# ESP32_RelayBoard.net
KiCad netlist of a schematic drawn in EasyEDA Pro
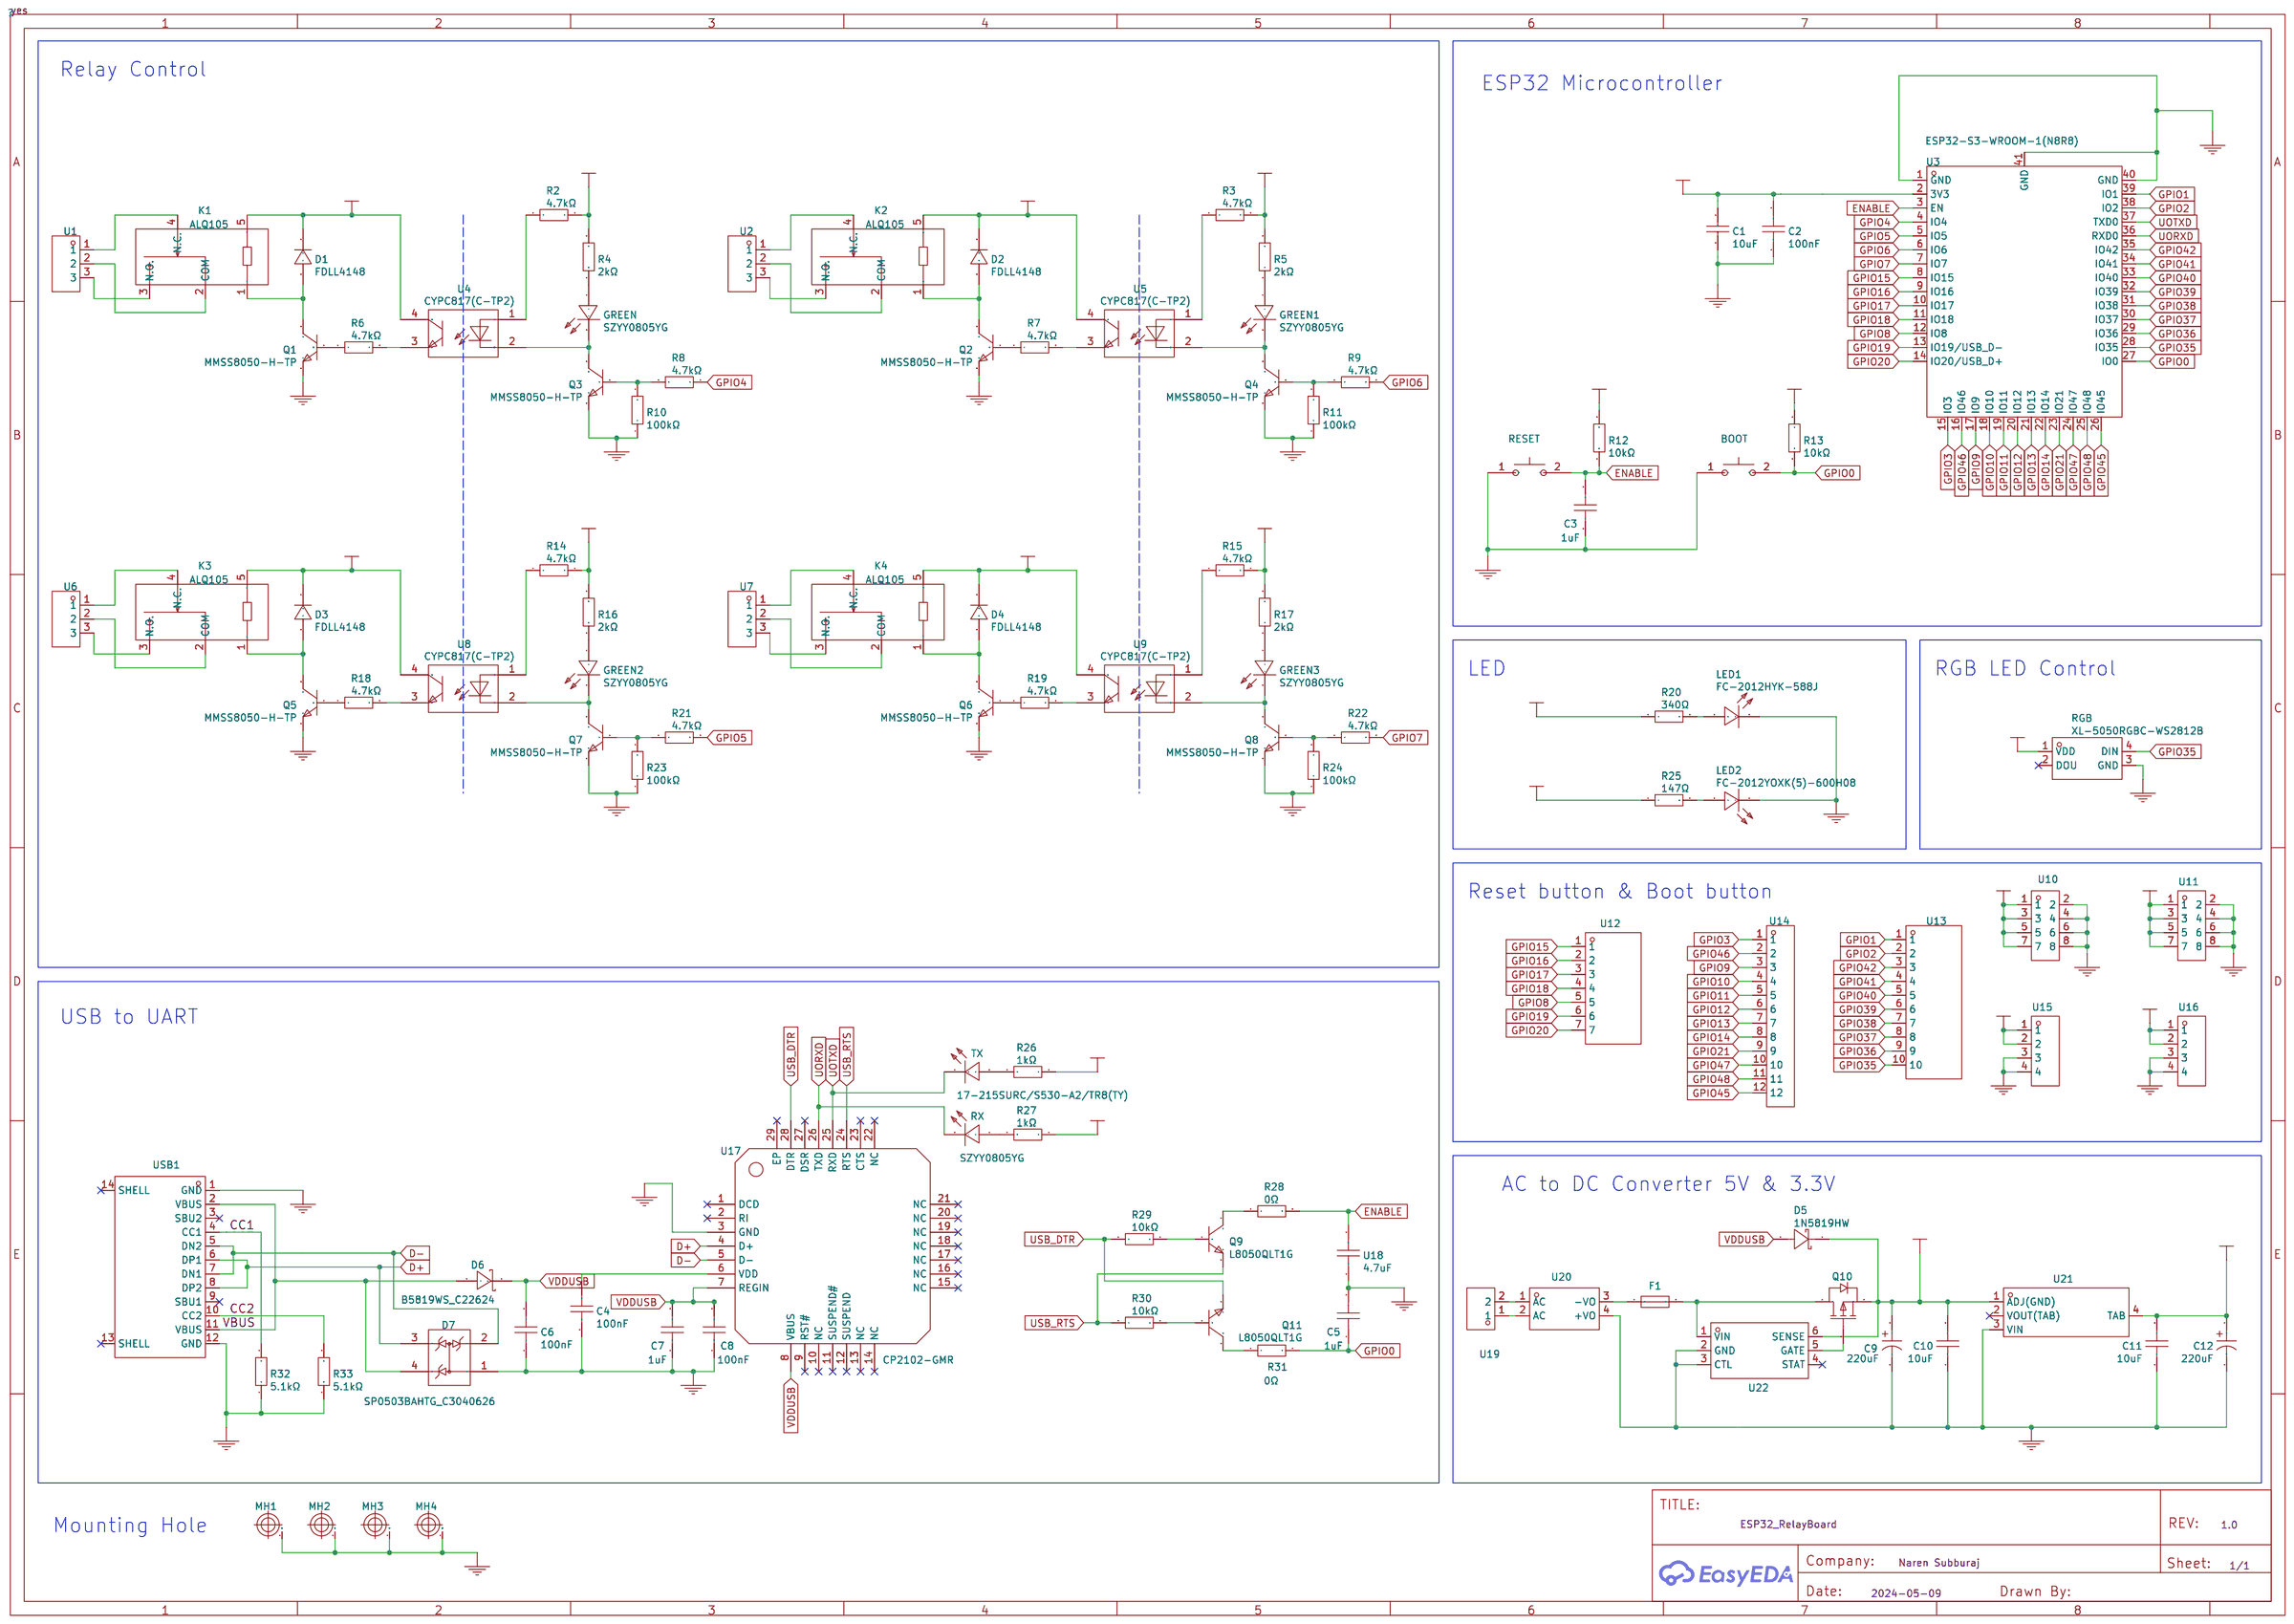
[diagram p0: schematic sheet]

(export (version "E")
  (design (tool "Eeschema 10.0.6"))
  (components
    (comp (ref "BOOT")
      (value "TS-1101S-C-B-B-B-A")
      (footprint "easyedapro:SW-SMD_L6.0-W3.5-LS8.0")
      (fields (field (name "Manufacturer") "XKB Connectivity(中国星坤)"))
      (libsource (lib "easyedapro") (part "TS-1101S-C-B-B-B-A"))
    )
    (comp (ref "C1")
      (value "10uF")
      (footprint "easyedapro:C0402")
      (fields
        (field (name "Manufacturer Part") "CC0402MRX5R5BB106")
        (field (name "Manufacturer") "YAGEO(国巨)")
      )
      (libsource (lib "") (part "10uF_1"))
    )
    (comp (ref "C2")
      (value "100nF")
      (footprint "easyedapro:C0402")
      (fields
        (field (name "Manufacturer Part") "CSA0402X7R104K250GT")
        (field (name "Manufacturer") "HRE(芯声)")
      )
      (libsource (lib "easyedapro") (part "100nF"))
    )
    (comp (ref "C3")
      (value "1uF")
      (footprint "easyedapro:C0402")
      (fields
        (field (name "Manufacturer Part") "HGC0402R5105K500NTEJ")
        (field (name "Manufacturer") "Chinocera(华瓷)")
      )
      (libsource (lib "easyedapro") (part "1uF"))
    )
    (comp (ref "C4")
      (value "100nF")
      (footprint "easyedapro:C0402")
      (fields
        (field (name "Manufacturer Part") "CSA0402X7R104K250GT")
        (field (name "Manufacturer") "HRE(芯声)")
      )
      (libsource (lib "easyedapro") (part "100nF"))
    )
    (comp (ref "C5")
      (value "1uF")
      (footprint "easyedapro:C0402")
      (fields
        (field (name "Manufacturer Part") "HGC0402R5105K500NTEJ")
        (field (name "Manufacturer") "Chinocera(华瓷)")
      )
      (libsource (lib "easyedapro") (part "1uF"))
    )
    (comp (ref "C6")
      (value "100nF")
      (footprint "easyedapro:C0402")
      (fields
        (field (name "Manufacturer Part") "CSA0402X7R104K250GT")
        (field (name "Manufacturer") "HRE(芯声)")
      )
      (libsource (lib "easyedapro") (part "100nF"))
    )
    (comp (ref "C7")
      (value "1uF")
      (footprint "easyedapro:C0402")
      (fields
        (field (name "Manufacturer Part") "HGC0402R5105K500NTEJ")
        (field (name "Manufacturer") "Chinocera(华瓷)")
      )
      (libsource (lib "easyedapro") (part "1uF"))
    )
    (comp (ref "C8")
      (value "100nF")
      (footprint "easyedapro:C0402")
      (fields
        (field (name "Manufacturer Part") "CSA0402X7R104K250GT")
        (field (name "Manufacturer") "HRE(芯声)")
      )
      (libsource (lib "easyedapro") (part "100nF"))
    )
    (comp (ref "C9")
      (value "220uF")
      (footprint "easyedapro:CAP-SMD_BD6.3-L6.6-W6.6-LS7.2-FD")
      (fields
        (field (name "Manufacturer Part") "MVG 16V 220UF 6.3*7.7")
        (field (name "Manufacturer") "SAMYOUNG(韩国三莹)")
      )
      (libsource (lib "easyedapro") (part "220uF"))
    )
    (comp (ref "C10")
      (value "10uF")
      (footprint "easyedapro:C0805")
      (fields (field (name "Manufacturer Part") "0805F106M160NT") (field (name "Manufacturer") "FH(风华)"))
      (libsource (lib "easyedapro") (part "10uF"))
    )
    (comp (ref "C11")
      (value "10uF")
      (footprint "easyedapro:C0805")
      (fields (field (name "Manufacturer Part") "0805F106M160NT") (field (name "Manufacturer") "FH(风华)"))
      (libsource (lib "easyedapro") (part "10uF"))
    )
    (comp (ref "C12")
      (value "220uF")
      (footprint "easyedapro:CAP-SMD_BD6.3-L6.6-W6.6-LS7.2-FD")
      (fields
        (field (name "Manufacturer Part") "MVG 16V 220UF 6.3*7.7")
        (field (name "Manufacturer") "SAMYOUNG(韩国三莹)")
      )
      (libsource (lib "easyedapro") (part "220uF"))
    )
    (comp (ref "D1")
      (value "FDLL4148")
      (footprint "easyedapro:SOD-80_L3.5-W1.5-RD")
      (fields (field (name "Manufacturer") "onsemi(安森美)"))
      (libsource (lib "easyedapro") (part "FDLL4148"))
    )
    (comp (ref "D2")
      (value "FDLL4148")
      (footprint "easyedapro:SOD-80_L3.5-W1.5-RD")
      (fields (field (name "Manufacturer") "onsemi(安森美)"))
      (libsource (lib "easyedapro") (part "FDLL4148"))
    )
    (comp (ref "D3")
      (value "FDLL4148")
      (footprint "easyedapro:SOD-80_L3.5-W1.5-RD")
      (fields (field (name "Manufacturer") "onsemi(安森美)"))
      (libsource (lib "easyedapro") (part "FDLL4148"))
    )
    (comp (ref "D4")
      (value "FDLL4148")
      (footprint "easyedapro:SOD-80_L3.5-W1.5-RD")
      (fields (field (name "Manufacturer") "onsemi(安森美)"))
      (libsource (lib "easyedapro") (part "FDLL4148"))
    )
    (comp (ref "D5")
      (value "1N5819HW")
      (footprint "easyedapro:SOD-123_L2.7-W1.6-LS3.7-RD-1")
      (fields (field (name "Manufacturer") "TECH PUBLIC(台舟)"))
      (libsource (lib "easyedapro") (part "1N5819HW"))
    )
    (comp (ref "D6")
      (value "B5819WS_C22624")
      (footprint "easyedapro:SOD-323_L1.8-W1.3-LS2.5-RD")
      (fields (field (name "Manufacturer Part") "B5819WS") (field (name "Manufacturer") "CJ(江苏长电/长晶)"))
      (libsource (lib "easyedapro") (part "B5819WS_C22624"))
    )
    (comp (ref "D7")
      (value "SP0503BAHTG_C3040626")
      (footprint "easyedapro:SOT-143-4_L2.9-W1.3-P1.92-LS2.4-BL")
      (fields
        (field (name "Manufacturer Part") "SP0503BAHTG")
        (field (name "Manufacturer") "TECH PUBLIC(台舟)")
      )
      (libsource (lib "easyedapro") (part "SP0503BAHTG_C3040626"))
    )
    (comp (ref "F1")
      (value "BSMD0805-100-6V")
      (footprint "easyedapro:F0805")
      (fields (field (name "Manufacturer") "BHFUSE(佰宏)"))
      (libsource (lib "easyedapro") (part "BSMD0805-100-6V"))
    )
    (comp (ref "GREEN")
      (value "SZYY0805YG")
      (footprint "easyedapro:LED0805-R-RD_GREEN")
      (fields (field (name "Manufacturer") "yongyu(永裕光电)"))
      (libsource (lib "easyedapro") (part "SZYY0805YG"))
    )
    (comp (ref "GREEN1")
      (value "SZYY0805YG")
      (footprint "easyedapro:LED0805-R-RD_GREEN")
      (fields (field (name "Manufacturer") "yongyu(永裕光电)"))
      (libsource (lib "easyedapro") (part "SZYY0805YG"))
    )
    (comp (ref "GREEN2")
      (value "SZYY0805YG")
      (footprint "easyedapro:LED0805-R-RD_GREEN")
      (fields (field (name "Manufacturer") "yongyu(永裕光电)"))
      (libsource (lib "easyedapro") (part "SZYY0805YG"))
    )
    (comp (ref "GREEN3")
      (value "SZYY0805YG")
      (footprint "easyedapro:LED0805-R-RD_GREEN")
      (fields (field (name "Manufacturer") "yongyu(永裕光电)"))
      (libsource (lib "easyedapro") (part "SZYY0805YG"))
    )
    (comp (ref "K1")
      (value "ALQ105")
      (footprint "easyedapro:RELAY-TH_ALQ1XX")
      (fields (field (name "Manufacturer") "PANASONIC(松下)"))
      (libsource (lib "easyedapro") (part "ALQ105"))
    )
    (comp (ref "K2")
      (value "ALQ105")
      (footprint "easyedapro:RELAY-TH_ALQ1XX")
      (fields (field (name "Manufacturer") "PANASONIC(松下)"))
      (libsource (lib "easyedapro") (part "ALQ105"))
    )
    (comp (ref "K3")
      (value "ALQ105")
      (footprint "easyedapro:RELAY-TH_ALQ1XX")
      (fields (field (name "Manufacturer") "PANASONIC(松下)"))
      (libsource (lib "easyedapro") (part "ALQ105"))
    )
    (comp (ref "K4")
      (value "ALQ105")
      (footprint "easyedapro:RELAY-TH_ALQ1XX")
      (fields (field (name "Manufacturer") "PANASONIC(松下)"))
      (libsource (lib "easyedapro") (part "ALQ105"))
    )
    (comp (ref "LED1")
      (value "FC-2012HYK-588J")
      (footprint "easyedapro:LED0805-R-RD")
      (fields (field (name "Manufacturer Part") "NCD0805Y1") (field (name "Manufacturer") "国星光电"))
      (libsource (lib "easyedapro") (part "FC-2012HYK-588J"))
    )
    (comp (ref "LED2")
      (value "FC-2012YOXK(5)-600H08")
      (footprint "easyedapro:LED0805-RD_ORANGE")
      (fields (field (name "Manufacturer Part") "NCD0805O1") (field (name "Manufacturer") "国星光电"))
      (libsource (lib "easyedapro") (part "FC-2012YOXK(5)-600H08"))
    )
    (comp (ref "MH1")
      (value "M2-MOUNTING-HOLE")
      (footprint "easyedapro:M2-MOUNTING-HOLE")
      (libsource (lib "easyedapro") (part "M2-MOUNTING-HOLE"))
    )
    (comp (ref "MH2")
      (value "M2-MOUNTING-HOLE")
      (footprint "easyedapro:M2-MOUNTING-HOLE")
      (libsource (lib "") (part "M2-MOUNTING-HOLE_1"))
    )
    (comp (ref "MH3")
      (value "M2-MOUNTING-HOLE")
      (footprint "easyedapro:M2-MOUNTING-HOLE")
      (libsource (lib "") (part "M2-MOUNTING-HOLE_2"))
    )
    (comp (ref "MH4")
      (value "M2-MOUNTING-HOLE")
      (footprint "easyedapro:M2-MOUNTING-HOLE")
      (libsource (lib "easyedapro") (part "M2-MOUNTING-HOLE"))
    )
    (comp (ref "Q1")
      (value "MMSS8050-H-TP")
      (footprint "easyedapro:SOT-23-3_L2.9-W1.6-P1.90-LS2.8-BR")
      (fields (field (name "Manufacturer") "MCC(美微科)"))
      (libsource (lib "easyedapro") (part "MMSS8050-H-TP"))
    )
    (comp (ref "Q2")
      (value "MMSS8050-H-TP")
      (footprint "easyedapro:SOT-23-3_L2.9-W1.6-P1.90-LS2.8-BR")
      (fields (field (name "Manufacturer") "MCC(美微科)"))
      (libsource (lib "easyedapro") (part "MMSS8050-H-TP"))
    )
    (comp (ref "Q3")
      (value "MMSS8050-H-TP")
      (footprint "easyedapro:SOT-23-3_L2.9-W1.6-P1.90-LS2.8-BR")
      (fields (field (name "Manufacturer") "MCC(美微科)"))
      (libsource (lib "easyedapro") (part "MMSS8050-H-TP"))
    )
    (comp (ref "Q4")
      (value "MMSS8050-H-TP")
      (footprint "easyedapro:SOT-23-3_L2.9-W1.6-P1.90-LS2.8-BR")
      (fields (field (name "Manufacturer") "MCC(美微科)"))
      (libsource (lib "easyedapro") (part "MMSS8050-H-TP"))
    )
    (comp (ref "Q5")
      (value "MMSS8050-H-TP")
      (footprint "easyedapro:SOT-23-3_L2.9-W1.6-P1.90-LS2.8-BR")
      (fields (field (name "Manufacturer") "MCC(美微科)"))
      (libsource (lib "easyedapro") (part "MMSS8050-H-TP"))
    )
    (comp (ref "Q6")
      (value "MMSS8050-H-TP")
      (footprint "easyedapro:SOT-23-3_L2.9-W1.6-P1.90-LS2.8-BR")
      (fields (field (name "Manufacturer") "MCC(美微科)"))
      (libsource (lib "easyedapro") (part "MMSS8050-H-TP"))
    )
    (comp (ref "Q7")
      (value "MMSS8050-H-TP")
      (footprint "easyedapro:SOT-23-3_L2.9-W1.6-P1.90-LS2.8-BR")
      (fields (field (name "Manufacturer") "MCC(美微科)"))
      (libsource (lib "easyedapro") (part "MMSS8050-H-TP"))
    )
    (comp (ref "Q8")
      (value "MMSS8050-H-TP")
      (footprint "easyedapro:SOT-23-3_L2.9-W1.6-P1.90-LS2.8-BR")
      (fields (field (name "Manufacturer") "MCC(美微科)"))
      (libsource (lib "easyedapro") (part "MMSS8050-H-TP"))
    )
    (comp (ref "Q9")
      (value "L8050QLT1G")
      (footprint "easyedapro:SOT-23-3_L2.9-W1.3-P1.90-LS2.4-BR")
      (fields (field (name "Manufacturer") "LRC(乐山无线电)"))
      (libsource (lib "easyedapro") (part "L8050QLT1G"))
    )
    (comp (ref "Q10")
      (value "FDN306P")
      (footprint "easyedapro:SOT-23-3_L3.0-W1.7-P0.95-LS2.9-BR")
      (fields (field (name "Manufacturer") "onsemi(安森美)"))
      (libsource (lib "easyedapro") (part "FDN306P"))
    )
    (comp (ref "Q11")
      (value "L8050QLT1G")
      (footprint "easyedapro:SOT-23-3_L2.9-W1.3-P1.90-LS2.4-BR")
      (fields (field (name "Manufacturer") "LRC(乐山无线电)"))
      (libsource (lib "") (part "L8050QLT1G_1"))
    )
    (comp (ref "R2")
      (value "4.7kΩ")
      (footprint "easyedapro:R0805")
      (fields
        (field (name "Manufacturer Part") "0805W8F4701T5E")
        (field (name "Manufacturer") "UNI-ROYAL(厚声)")
      )
      (libsource (lib "easyedapro") (part "4.7kΩ"))
    )
    (comp (ref "R3")
      (value "4.7kΩ")
      (footprint "easyedapro:R0805")
      (fields
        (field (name "Manufacturer Part") "0805W8F4701T5E")
        (field (name "Manufacturer") "UNI-ROYAL(厚声)")
      )
      (libsource (lib "easyedapro") (part "4.7kΩ"))
    )
    (comp (ref "R4")
      (value "2kΩ")
      (footprint "easyedapro:R0805")
      (fields
        (field (name "Manufacturer Part") "0805W8F2001T5E")
        (field (name "Manufacturer") "UNI-ROYAL(厚声)")
      )
      (libsource (lib "easyedapro") (part "2kΩ"))
    )
    (comp (ref "R5")
      (value "2kΩ")
      (footprint "easyedapro:R0805")
      (fields
        (field (name "Manufacturer Part") "0805W8F2001T5E")
        (field (name "Manufacturer") "UNI-ROYAL(厚声)")
      )
      (libsource (lib "easyedapro") (part "2kΩ"))
    )
    (comp (ref "R6")
      (value "4.7kΩ")
      (footprint "easyedapro:R0805")
      (fields
        (field (name "Manufacturer Part") "0805W8F4701T5E")
        (field (name "Manufacturer") "UNI-ROYAL(厚声)")
      )
      (libsource (lib "easyedapro") (part "4.7kΩ"))
    )
    (comp (ref "R7")
      (value "4.7kΩ")
      (footprint "easyedapro:R0805")
      (fields
        (field (name "Manufacturer Part") "0805W8F4701T5E")
        (field (name "Manufacturer") "UNI-ROYAL(厚声)")
      )
      (libsource (lib "easyedapro") (part "4.7kΩ"))
    )
    (comp (ref "R8")
      (value "4.7kΩ")
      (footprint "easyedapro:R0805")
      (fields
        (field (name "Manufacturer Part") "0805W8F4701T5E")
        (field (name "Manufacturer") "UNI-ROYAL(厚声)")
      )
      (libsource (lib "easyedapro") (part "4.7kΩ"))
    )
    (comp (ref "R9")
      (value "4.7kΩ")
      (footprint "easyedapro:R0805")
      (fields
        (field (name "Manufacturer Part") "0805W8F4701T5E")
        (field (name "Manufacturer") "UNI-ROYAL(厚声)")
      )
      (libsource (lib "easyedapro") (part "4.7kΩ"))
    )
    (comp (ref "R10")
      (value "100kΩ")
      (footprint "easyedapro:R0805")
      (fields
        (field (name "Manufacturer Part") "0805W8F1003T5E")
        (field (name "Manufacturer") "UNI-ROYAL(厚声)")
      )
      (libsource (lib "easyedapro") (part "100kΩ"))
    )
    (comp (ref "R11")
      (value "100kΩ")
      (footprint "easyedapro:R0805")
      (fields
        (field (name "Manufacturer Part") "0805W8F1003T5E")
        (field (name "Manufacturer") "UNI-ROYAL(厚声)")
      )
      (libsource (lib "easyedapro") (part "100kΩ"))
    )
    (comp (ref "R12")
      (value "10kΩ")
      (footprint "easyedapro:R0402")
      (fields (field (name "Manufacturer Part") "RT0402DRE0710KL") (field (name "Manufacturer") "YAGEO(国巨)"))
      (libsource (lib "easyedapro") (part "10kΩ"))
    )
    (comp (ref "R13")
      (value "10kΩ")
      (footprint "easyedapro:R0402")
      (fields (field (name "Manufacturer Part") "RT0402DRE0710KL") (field (name "Manufacturer") "YAGEO(国巨)"))
      (libsource (lib "easyedapro") (part "10kΩ"))
    )
    (comp (ref "R14")
      (value "4.7kΩ")
      (footprint "easyedapro:R0805")
      (fields
        (field (name "Manufacturer Part") "0805W8F4701T5E")
        (field (name "Manufacturer") "UNI-ROYAL(厚声)")
      )
      (libsource (lib "easyedapro") (part "4.7kΩ"))
    )
    (comp (ref "R15")
      (value "4.7kΩ")
      (footprint "easyedapro:R0805")
      (fields
        (field (name "Manufacturer Part") "0805W8F4701T5E")
        (field (name "Manufacturer") "UNI-ROYAL(厚声)")
      )
      (libsource (lib "easyedapro") (part "4.7kΩ"))
    )
    (comp (ref "R16")
      (value "2kΩ")
      (footprint "easyedapro:R0805")
      (fields
        (field (name "Manufacturer Part") "0805W8F2001T5E")
        (field (name "Manufacturer") "UNI-ROYAL(厚声)")
      )
      (libsource (lib "easyedapro") (part "2kΩ"))
    )
    (comp (ref "R17")
      (value "2kΩ")
      (footprint "easyedapro:R0805")
      (fields
        (field (name "Manufacturer Part") "0805W8F2001T5E")
        (field (name "Manufacturer") "UNI-ROYAL(厚声)")
      )
      (libsource (lib "easyedapro") (part "2kΩ"))
    )
    (comp (ref "R18")
      (value "4.7kΩ")
      (footprint "easyedapro:R0805")
      (fields
        (field (name "Manufacturer Part") "0805W8F4701T5E")
        (field (name "Manufacturer") "UNI-ROYAL(厚声)")
      )
      (libsource (lib "easyedapro") (part "4.7kΩ"))
    )
    (comp (ref "R19")
      (value "4.7kΩ")
      (footprint "easyedapro:R0805")
      (fields
        (field (name "Manufacturer Part") "0805W8F4701T5E")
        (field (name "Manufacturer") "UNI-ROYAL(厚声)")
      )
      (libsource (lib "easyedapro") (part "4.7kΩ"))
    )
    (comp (ref "R20")
      (value "340Ω")
      (footprint "easyedapro:R0805")
      (fields (field (name "Manufacturer Part") "CR0805F83400G") (field (name "Manufacturer") "LIZ(丽智电子)"))
      (libsource (lib "easyedapro") (part "340Ω"))
    )
    (comp (ref "R21")
      (value "4.7kΩ")
      (footprint "easyedapro:R0805")
      (fields
        (field (name "Manufacturer Part") "0805W8F4701T5E")
        (field (name "Manufacturer") "UNI-ROYAL(厚声)")
      )
      (libsource (lib "easyedapro") (part "4.7kΩ"))
    )
    (comp (ref "R22")
      (value "4.7kΩ")
      (footprint "easyedapro:R0805")
      (fields
        (field (name "Manufacturer Part") "0805W8F4701T5E")
        (field (name "Manufacturer") "UNI-ROYAL(厚声)")
      )
      (libsource (lib "easyedapro") (part "4.7kΩ"))
    )
    (comp (ref "R23")
      (value "100kΩ")
      (footprint "easyedapro:R0805")
      (fields
        (field (name "Manufacturer Part") "0805W8F1003T5E")
        (field (name "Manufacturer") "UNI-ROYAL(厚声)")
      )
      (libsource (lib "easyedapro") (part "100kΩ"))
    )
    (comp (ref "R24")
      (value "100kΩ")
      (footprint "easyedapro:R0805")
      (fields
        (field (name "Manufacturer Part") "0805W8F1003T5E")
        (field (name "Manufacturer") "UNI-ROYAL(厚声)")
      )
      (libsource (lib "easyedapro") (part "100kΩ"))
    )
    (comp (ref "R25")
      (value "147Ω")
      (footprint "easyedapro:R0805")
      (fields (field (name "Manufacturer Part") "CR0805-FX-1470ELF") (field (name "Manufacturer") "BOURNS"))
      (libsource (lib "easyedapro") (part "147Ω"))
    )
    (comp (ref "R26")
      (value "1kΩ")
      (footprint "easyedapro:R0805")
      (fields (field (name "Manufacturer Part") "RMC08051K5%N") (field (name "Manufacturer") "Tyohm(幸亚电阻)"))
      (libsource (lib "easyedapro") (part "1kΩ"))
    )
    (comp (ref "R27")
      (value "1kΩ")
      (footprint "easyedapro:R0805")
      (fields (field (name "Manufacturer Part") "RMC08051K5%N") (field (name "Manufacturer") "Tyohm(幸亚电阻)"))
      (libsource (lib "easyedapro") (part "1kΩ"))
    )
    (comp (ref "R28")
      (value "0Ω")
      (footprint "easyedapro:R0402")
      (fields (field (name "Manufacturer Part") "RC0402FR-070RL") (field (name "Manufacturer") "YAGEO(国巨)"))
      (libsource (lib "easyedapro") (part "0Ω"))
    )
    (comp (ref "R29")
      (value "10kΩ")
      (footprint "easyedapro:R0402")
      (fields (field (name "Manufacturer Part") "RT0402DRE0710KL") (field (name "Manufacturer") "YAGEO(国巨)"))
      (libsource (lib "easyedapro") (part "10kΩ"))
    )
    (comp (ref "R30")
      (value "10kΩ")
      (footprint "easyedapro:R0402")
      (fields (field (name "Manufacturer Part") "RT0402DRE0710KL") (field (name "Manufacturer") "YAGEO(国巨)"))
      (libsource (lib "easyedapro") (part "10kΩ"))
    )
    (comp (ref "R31")
      (value "0Ω")
      (footprint "easyedapro:R0402")
      (fields (field (name "Manufacturer Part") "RC0402FR-070RL") (field (name "Manufacturer") "YAGEO(国巨)"))
      (libsource (lib "easyedapro") (part "0Ω"))
    )
    (comp (ref "R32")
      (value "5.1kΩ")
      (footprint "easyedapro:R0402")
      (fields (field (name "Manufacturer Part") "RMC04025.1K1%N") (field (name "Manufacturer") "Tyohm(幸亚电阻)"))
      (libsource (lib "easyedapro") (part "5.1kΩ"))
    )
    (comp (ref "R33")
      (value "5.1kΩ")
      (footprint "easyedapro:R0402")
      (fields (field (name "Manufacturer Part") "RMC04025.1K1%N") (field (name "Manufacturer") "Tyohm(幸亚电阻)"))
      (libsource (lib "easyedapro") (part "5.1kΩ"))
    )
    (comp (ref "RESET")
      (value "TS-1101S-C-B-B-B-A")
      (footprint "easyedapro:SW-SMD_L6.0-W3.5-LS8.0")
      (fields (field (name "Manufacturer") "XKB Connectivity(中国星坤)"))
      (libsource (lib "easyedapro") (part "TS-1101S-C-B-B-B-A"))
    )
    (comp (ref "RGB")
      (value "XL-5050RGBC-WS2812B")
      (footprint "easyedapro:LED-SMD_4P-L5.0-W5.0-BL_XL-5050RGBC")
      (fields (field (name "Manufacturer") "XINGLIGHT(成兴光)"))
      (libsource (lib "easyedapro") (part "XL-5050RGBC-WS2812B"))
    )
    (comp (ref "RX")
      (value "SZYY0805YG")
      (footprint "easyedapro:LED0805-R-RD_GREEN")
      (fields (field (name "Manufacturer") "yongyu(永裕光电)"))
      (libsource (lib "easyedapro") (part "SZYY0805YG"))
    )
    (comp (ref "TX")
      (value "17-215SURC/S530-A2/TR8(TY)")
      (footprint "easyedapro:LED0805-RD_RED")
      (fields
        (field (name "Manufacturer Part") "17-215SURC/S530-A2/TR8")
        (field (name "Manufacturer") "EVERLIGHT(亿光)")
      )
      (libsource (lib "easyedapro") (part "17-215SURC/S530-A2/TR8(TY)"))
    )
    (comp (ref "U1")
      (value "DB128L-5.08-3P-BK-S")
      (footprint "easyedapro:CONN-TH_3P-P5.08_DB128L-5.08-3P-BK-S")
      (fields (field (name "Manufacturer") "DORABO(地博电气)"))
      (libsource (lib "easyedapro") (part "DB128L-5.08-3P-BK-S"))
    )
    (comp (ref "U2")
      (value "DB128L-5.08-3P-BK-S")
      (footprint "easyedapro:CONN-TH_3P-P5.08_DB128L-5.08-3P-BK-S")
      (fields (field (name "Manufacturer") "DORABO(地博电气)"))
      (libsource (lib "easyedapro") (part "DB128L-5.08-3P-BK-S"))
    )
    (comp (ref "U3")
      (value "ESP32-S3-WROOM-1(N8R8)")
      (footprint "easyedapro:WIRELM-SMD_ESP32-S3-WROOM-1")
      (fields
        (field (name "Manufacturer Part") "ESP32-S3-WROOM-1-N8R8")
        (field (name "Manufacturer") "ESPRESSIF(乐鑫)")
      )
      (libsource (lib "easyedapro") (part "ESP32-S3-WROOM-1(N8R8)"))
    )
    (comp (ref "U4")
      (value "CYPC817(C-TP2)")
      (footprint "easyedapro:SOP-4_L6.4-W4.6-P2.54-LS10.2-TL")
      (fields (field (name "Manufacturer") "OCIC(卓睿科)"))
      (libsource (lib "easyedapro") (part "CYPC817(C-TP2)"))
    )
    (comp (ref "U5")
      (value "CYPC817(C-TP2)")
      (footprint "easyedapro:SOP-4_L6.4-W4.6-P2.54-LS10.2-TL")
      (fields (field (name "Manufacturer") "OCIC(卓睿科)"))
      (libsource (lib "easyedapro") (part "CYPC817(C-TP2)"))
    )
    (comp (ref "U6")
      (value "DB128L-5.08-3P-BK-S")
      (footprint "easyedapro:CONN-TH_3P-P5.08_DB128L-5.08-3P-BK-S")
      (fields (field (name "Manufacturer") "DORABO(地博电气)"))
      (libsource (lib "easyedapro") (part "DB128L-5.08-3P-BK-S"))
    )
    (comp (ref "U7")
      (value "DB128L-5.08-3P-BK-S")
      (footprint "easyedapro:CONN-TH_3P-P5.08_DB128L-5.08-3P-BK-S")
      (fields (field (name "Manufacturer") "DORABO(地博电气)"))
      (libsource (lib "easyedapro") (part "DB128L-5.08-3P-BK-S"))
    )
    (comp (ref "U8")
      (value "CYPC817(C-TP2)")
      (footprint "easyedapro:SOP-4_L6.4-W4.6-P2.54-LS10.2-TL")
      (fields (field (name "Manufacturer") "OCIC(卓睿科)"))
      (libsource (lib "easyedapro") (part "CYPC817(C-TP2)"))
    )
    (comp (ref "U9")
      (value "CYPC817(C-TP2)")
      (footprint "easyedapro:SOP-4_L6.4-W4.6-P2.54-LS10.2-TL")
      (fields (field (name "Manufacturer") "OCIC(卓睿科)"))
      (libsource (lib "easyedapro") (part "CYPC817(C-TP2)"))
    )
    (comp (ref "U10")
      (value "ZX-PM2.54-2-4PY")
      (footprint "easyedapro:HDR-TH_8P-P2.54-V-F-R2-C4-S2.54")
      (fields (field (name "Manufacturer") "Megastar(兆星)"))
      (libsource (lib "easyedapro") (part "ZX-PM2.54-2-4PY"))
    )
    (comp (ref "U11")
      (value "ZX-PM2.54-2-4PY")
      (footprint "easyedapro:HDR-TH_8P-P2.54-V-F-R2-C4-S2.54")
      (fields (field (name "Manufacturer") "Megastar(兆星)"))
      (libsource (lib "easyedapro") (part "ZX-PM2.54-2-4PY"))
    )
    (comp (ref "U12")
      (value "A2541HWV-7P")
      (footprint "easyedapro:HDR-TH_7P-P2.54-V_A2541HWV-7P")
      (fields (field (name "Manufacturer") "CJT(长江连接器)"))
      (libsource (lib "easyedapro") (part "A2541HWV-7P"))
    )
    (comp (ref "U13")
      (value "A2541HWV-10P")
      (footprint "easyedapro:HDR-TH_10P-P2.54-V-F-1")
      (fields (field (name "Manufacturer") "CJT(长江连接器)"))
      (libsource (lib "easyedapro") (part "A2541HWV-10P"))
    )
    (comp (ref "U14")
      (value "ZX-PM2.54-1-12PY")
      (footprint "easyedapro:HDR-TH_12P-P2.54-V-F")
      (fields (field (name "Manufacturer") "Megastar(兆星)"))
      (libsource (lib "easyedapro") (part "ZX-PM2.54-1-12PY"))
    )
    (comp (ref "U15")
      (value "HB-PH3-25414PB2GOP")
      (footprint "easyedapro:HDR-TH_4P-P2.54-V-M")
      (fields (field (name "Manufacturer") "HANBO(汉博)"))
      (libsource (lib "easyedapro") (part "HB-PH3-25414PB2GOP"))
    )
    (comp (ref "U16")
      (value "HB-PH3-25414PB2GOP")
      (footprint "easyedapro:HDR-TH_4P-P2.54-V-M")
      (fields (field (name "Manufacturer") "HANBO(汉博)"))
      (libsource (lib "easyedapro") (part "HB-PH3-25414PB2GOP"))
    )
    (comp (ref "U17")
      (value "CP2102-GMR")
      (footprint "easyedapro:WQFN-28_L5.0-W5.0-P0.50-BL-EP3.2")
      (fields (field (name "Manufacturer") "SKYWORKS/SILICON LABS(芯科)"))
      (libsource (lib "easyedapro") (part "CP2102-GMR"))
    )
    (comp (ref "U18")
      (value "4.7uF")
      (footprint "easyedapro:C0402")
      (fields
        (field (name "Manufacturer Part") "HGC0402R5475K100NTEJ")
        (field (name "Manufacturer") "Chinocera(华瓷)")
      )
      (libsource (lib "easyedapro") (part "4.7uF"))
    )
    (comp (ref "U19")
      (value "DB128L-5.08-2P-BK-S")
      (footprint "easyedapro:CONN-TH_2P-P5.08_DB128L-5.08-2P-BK-S")
      (fields (field (name "Manufacturer") "DORABO(地博电气)"))
      (libsource (lib "easyedapro") (part "DB128L-5.08-2P-BK-S"))
    )
    (comp (ref "U20")
      (value "HLK-10M05")
      (footprint "easyedapro:PWRM-TH_HLK-10M05")
      (fields (field (name "Manufacturer") "HI-LINK(海凌科)"))
      (libsource (lib "easyedapro") (part "HLK-10M05"))
    )
    (comp (ref "U21")
      (value "AMS1117-3.3_C347222")
      (footprint "easyedapro:SOT-223-4_L6.5-W3.5-P2.30-LS7.0-BR")
      (fields (field (name "Manufacturer Part") "AMS1117-3.3") (field (name "Manufacturer") "UMW(友台半导体)"))
      (libsource (lib "easyedapro") (part "AMS1117-3.3_C347222"))
    )
    (comp (ref "U22")
      (value "LTC4412HVIS6#TRPBF")
      (footprint "easyedapro:TSOT-23-6_L2.9-W1.6-P0.95-LS2.8-BR")
      (fields (field (name "Manufacturer") "ADI(亚德诺)"))
      (libsource (lib "easyedapro") (part "LTC4412HVIS6#TRPBF"))
    )
    (comp (ref "USB1")
      (value "TYPE-C 16PIN 2MD(073)")
      (footprint "easyedapro:USB-C-SMD_TYPE-C-6PIN-2MD-073")
      (fields (field (name "Manufacturer") "SHOU HAN(首韩)"))
      (libsource (lib "easyedapro") (part "TYPE-C 16PIN 2MD(073)"))
    )
  )
  (nets
    (net (code "1") (name "+5V") (class "Default")
      (node (ref "C10") (pin "2") (pinfunction "2_2") (pintype "unspecified"))
      (node (ref "C9") (pin "1") (pinfunction "1_1") (pintype "input"))
      (node (ref "D1") (pin "1") (pinfunction "C_1") (pintype "unspecified"))
      (node (ref "D2") (pin "1") (pinfunction "C_1") (pintype "unspecified"))
      (node (ref "D3") (pin "1") (pinfunction "C_1") (pintype "unspecified"))
      (node (ref "D4") (pin "1") (pinfunction "C_1") (pintype "unspecified"))
      (node (ref "D5") (pin "1") (pinfunction "K_1") (pintype "unspecified"))
      (node (ref "K1") (pin "5") (pinfunction "5_5") (pintype "unspecified"))
      (node (ref "K2") (pin "5") (pinfunction "5_5") (pintype "unspecified"))
      (node (ref "K3") (pin "5") (pinfunction "5_5") (pintype "unspecified"))
      (node (ref "K4") (pin "5") (pinfunction "5_5") (pintype "unspecified"))
      (node (ref "Q10") (pin "2") (pinfunction "S_2") (pintype "unspecified"))
      (node (ref "R20") (pin "1") (pinfunction "1_1") (pintype "unspecified"))
      (node (ref "RGB") (pin "1") (pinfunction "VDD_1") (pintype "unspecified"))
      (node (ref "U11") (pin "1") (pinfunction "1_1") (pintype "unspecified"))
      (node (ref "U11") (pin "3") (pinfunction "3_3") (pintype "unspecified"))
      (node (ref "U11") (pin "5") (pinfunction "5_5") (pintype "unspecified"))
      (node (ref "U11") (pin "7") (pinfunction "7_7") (pintype "unspecified"))
      (node (ref "U16") (pin "1") (pinfunction "1_1") (pintype "unspecified"))
      (node (ref "U16") (pin "2") (pinfunction "2_2") (pintype "unspecified"))
      (node (ref "U21") (pin "1") (pinfunction "ADJ(GND)_1") (pintype "unspecified"))
      (node (ref "U22") (pin "6") (pinfunction "SENSE_6") (pintype "unspecified"))
      (node (ref "U4") (pin "4") (pinfunction "COL_4") (pintype "unspecified"))
      (node (ref "U5") (pin "4") (pinfunction "COL_4") (pintype "unspecified"))
      (node (ref "U8") (pin "4") (pinfunction "COL_4") (pintype "unspecified"))
      (node (ref "U9") (pin "4") (pinfunction "COL_4") (pintype "unspecified"))
    )
    (net (code "2") (name "/CC1") (class "Default")
      (node (ref "R32") (pin "2") (pinfunction "2_2") (pintype "unspecified"))
      (node (ref "USB1") (pin "4") (pinfunction "CC1_4") (pintype "unspecified"))
    )
    (net (code "3") (name "/CC2") (class "Default")
      (node (ref "R33") (pin "2") (pinfunction "2_2") (pintype "unspecified"))
      (node (ref "USB1") (pin "10") (pinfunction "CC2_10") (pintype "unspecified"))
    )
    (net (code "4") (name "/VBUS") (class "Default")
      (node (ref "D6") (pin "2") (pinfunction "A_2") (pintype "unspecified"))
      (node (ref "D7") (pin "4") (pinfunction "4_4") (pintype "input"))
      (node (ref "USB1") (pin "11") (pinfunction "VBUS_11") (pintype "unspecified"))
      (node (ref "USB1") (pin "2") (pinfunction "VBUS_2") (pintype "unspecified"))
    )
    (net (code "5") (name "3V3") (class "Default")
      (node (ref "C1") (pin "2") (pinfunction "2_2") (pintype "input"))
      (node (ref "C11") (pin "2") (pinfunction "2_2") (pintype "unspecified"))
      (node (ref "C12") (pin "1") (pinfunction "1_1") (pintype "input"))
      (node (ref "C2") (pin "2") (pinfunction "2_2") (pintype "unspecified"))
      (node (ref "R12") (pin "2") (pinfunction "2_2") (pintype "unspecified"))
      (node (ref "R13") (pin "2") (pinfunction "2_2") (pintype "unspecified"))
      (node (ref "R14") (pin "2") (pinfunction "2_2") (pintype "input"))
      (node (ref "R15") (pin "2") (pinfunction "2_2") (pintype "input"))
      (node (ref "R16") (pin "2") (pinfunction "2_2") (pintype "input"))
      (node (ref "R17") (pin "2") (pinfunction "2_2") (pintype "input"))
      (node (ref "R2") (pin "2") (pinfunction "2_2") (pintype "input"))
      (node (ref "R25") (pin "1") (pinfunction "1_1") (pintype "unspecified"))
      (node (ref "R26") (pin "1") (pinfunction "1_1") (pintype "unspecified"))
      (node (ref "R27") (pin "1") (pinfunction "1_1") (pintype "unspecified"))
      (node (ref "R3") (pin "2") (pinfunction "2_2") (pintype "input"))
      (node (ref "R4") (pin "2") (pinfunction "2_2") (pintype "input"))
      (node (ref "R5") (pin "2") (pinfunction "2_2") (pintype "input"))
      (node (ref "U10") (pin "1") (pinfunction "1_1") (pintype "unspecified"))
      (node (ref "U10") (pin "3") (pinfunction "3_3") (pintype "unspecified"))
      (node (ref "U10") (pin "5") (pinfunction "5_5") (pintype "unspecified"))
      (node (ref "U10") (pin "7") (pinfunction "7_7") (pintype "unspecified"))
      (node (ref "U15") (pin "1") (pinfunction "1_1") (pintype "unspecified"))
      (node (ref "U15") (pin "2") (pinfunction "2_2") (pintype "unspecified"))
      (node (ref "U21") (pin "4") (pinfunction "TAB_4") (pintype "unspecified"))
      (node (ref "U3") (pin "2") (pinfunction "3V3_2") (pintype "unspecified"))
    )
    (net (code "6") (name "D+") (class "Default")
      (node (ref "D7") (pin "3") (pinfunction "3_3") (pintype "input"))
      (node (ref "U17") (pin "4") (pinfunction "D+_4") (pintype "unspecified"))
      (node (ref "USB1") (pin "6") (pinfunction "DP1_6") (pintype "unspecified"))
      (node (ref "USB1") (pin "8") (pinfunction "DP2_8") (pintype "unspecified"))
    )
    (net (code "7") (name "D-") (class "Default")
      (node (ref "D7") (pin "2") (pinfunction "2_2") (pintype "input"))
      (node (ref "U17") (pin "5") (pinfunction "D-_5") (pintype "unspecified"))
      (node (ref "USB1") (pin "5") (pinfunction "DN2_5") (pintype "unspecified"))
      (node (ref "USB1") (pin "7") (pinfunction "DN1_7") (pintype "unspecified"))
    )
    (net (code "8") (name "ENABLE") (class "Default")
      (node (ref "C3") (pin "2") (pinfunction "2_2") (pintype "unspecified"))
      (node (ref "R12") (pin "1") (pinfunction "1_1") (pintype "unspecified"))
      (node (ref "R28") (pin "2") (pinfunction "2_2") (pintype "input"))
      (node (ref "RESET") (pin "2") (pinfunction "2_2") (pintype "unspecified"))
      (node (ref "U18") (pin "2") (pinfunction "2_2") (pintype "unspecified"))
      (node (ref "U3") (pin "3") (pinfunction "EN_3") (pintype "unspecified"))
    )
    (net (code "9") (name "GND") (class "Default")
      (node (ref "BOOT") (pin "1") (pinfunction "1_1") (pintype "unspecified"))
      (node (ref "C1") (pin "1") (pinfunction "1_1") (pintype "input"))
      (node (ref "C10") (pin "1") (pinfunction "1_1") (pintype "unspecified"))
      (node (ref "C11") (pin "1") (pinfunction "1_1") (pintype "unspecified"))
      (node (ref "C12") (pin "2") (pinfunction "2_2") (pintype "input"))
      (node (ref "C2") (pin "1") (pinfunction "1_1") (pintype "unspecified"))
      (node (ref "C3") (pin "1") (pinfunction "1_1") (pintype "unspecified"))
      (node (ref "C4") (pin "1") (pinfunction "1_1") (pintype "unspecified"))
      (node (ref "C5") (pin "2") (pinfunction "2_2") (pintype "unspecified"))
      (node (ref "C6") (pin "1") (pinfunction "1_1") (pintype "unspecified"))
      (node (ref "C7") (pin "1") (pinfunction "1_1") (pintype "unspecified"))
      (node (ref "C8") (pin "1") (pinfunction "1_1") (pintype "unspecified"))
      (node (ref "C9") (pin "2") (pinfunction "2_2") (pintype "input"))
      (node (ref "D7") (pin "1") (pinfunction "1_1") (pintype "input"))
      (node (ref "LED1") (pin "2") (pinfunction "K_2") (pintype "unspecified"))
      (node (ref "LED2") (pin "1") (pinfunction "-_1") (pintype "unspecified"))
      (node (ref "MH1") (pin "1") (pinfunction "GND_1") (pintype "unspecified"))
      (node (ref "MH2") (pin "1") (pinfunction "GND_1") (pintype "unspecified"))
      (node (ref "MH3") (pin "1") (pinfunction "GND_1") (pintype "unspecified"))
      (node (ref "MH4") (pin "1") (pinfunction "GND_1") (pintype "unspecified"))
      (node (ref "Q1") (pin "2") (pinfunction "E_2") (pintype "input"))
      (node (ref "Q2") (pin "2") (pinfunction "E_2") (pintype "input"))
      (node (ref "Q3") (pin "2") (pinfunction "E_2") (pintype "input"))
      (node (ref "Q4") (pin "2") (pinfunction "E_2") (pintype "input"))
      (node (ref "Q5") (pin "2") (pinfunction "E_2") (pintype "input"))
      (node (ref "Q6") (pin "2") (pinfunction "E_2") (pintype "input"))
      (node (ref "Q7") (pin "2") (pinfunction "E_2") (pintype "input"))
      (node (ref "Q8") (pin "2") (pinfunction "E_2") (pintype "input"))
      (node (ref "R10") (pin "1") (pinfunction "1_1") (pintype "unspecified"))
      (node (ref "R11") (pin "1") (pinfunction "1_1") (pintype "unspecified"))
      (node (ref "R23") (pin "1") (pinfunction "1_1") (pintype "unspecified"))
      (node (ref "R24") (pin "1") (pinfunction "1_1") (pintype "unspecified"))
      (node (ref "R32") (pin "1") (pinfunction "1_1") (pintype "unspecified"))
      (node (ref "R33") (pin "1") (pinfunction "1_1") (pintype "unspecified"))
      (node (ref "RESET") (pin "1") (pinfunction "1_1") (pintype "unspecified"))
      (node (ref "RGB") (pin "3") (pinfunction "GND_3") (pintype "unspecified"))
      (node (ref "U10") (pin "2") (pinfunction "2_2") (pintype "unspecified"))
      (node (ref "U10") (pin "4") (pinfunction "4_4") (pintype "unspecified"))
      (node (ref "U10") (pin "6") (pinfunction "6_6") (pintype "unspecified"))
      (node (ref "U10") (pin "8") (pinfunction "8_8") (pintype "unspecified"))
      (node (ref "U11") (pin "2") (pinfunction "2_2") (pintype "unspecified"))
      (node (ref "U11") (pin "4") (pinfunction "4_4") (pintype "unspecified"))
      (node (ref "U11") (pin "6") (pinfunction "6_6") (pintype "unspecified"))
      (node (ref "U11") (pin "8") (pinfunction "8_8") (pintype "unspecified"))
      (node (ref "U15") (pin "3") (pinfunction "3_3") (pintype "unspecified"))
      (node (ref "U15") (pin "4") (pinfunction "4_4") (pintype "unspecified"))
      (node (ref "U16") (pin "3") (pinfunction "3_3") (pintype "unspecified"))
      (node (ref "U16") (pin "4") (pinfunction "4_4") (pintype "unspecified"))
      (node (ref "U17") (pin "3") (pinfunction "GND_3") (pintype "unspecified"))
      (node (ref "U18") (pin "1") (pinfunction "1_1") (pintype "unspecified"))
      (node (ref "U20") (pin "4") (pinfunction "+VO_4") (pintype "unspecified"))
      (node (ref "U21") (pin "3") (pinfunction "VIN_3") (pintype "unspecified"))
      (node (ref "U22") (pin "2") (pinfunction "GND_2") (pintype "unspecified"))
      (node (ref "U22") (pin "3") (pinfunction "CTL_3") (pintype "unspecified"))
      (node (ref "U3") (pin "1") (pinfunction "GND_1") (pintype "unspecified"))
      (node (ref "U3") (pin "40") (pinfunction "GND_40") (pintype "unspecified"))
      (node (ref "U3") (pin "41") (pinfunction "GND_41") (pintype "unspecified"))
      (node (ref "USB1") (pin "1") (pinfunction "GND_1") (pintype "unspecified"))
      (node (ref "USB1") (pin "12") (pinfunction "GND_12") (pintype "unspecified"))
    )
    (net (code "10") (name "GPIO0") (class "Default")
      (node (ref "BOOT") (pin "2") (pinfunction "2_2") (pintype "unspecified"))
      (node (ref "C5") (pin "1") (pinfunction "1_1") (pintype "unspecified"))
      (node (ref "R13") (pin "1") (pinfunction "1_1") (pintype "unspecified"))
      (node (ref "R31") (pin "2") (pinfunction "2_2") (pintype "input"))
      (node (ref "U3") (pin "27") (pinfunction "IO0_27") (pintype "unspecified"))
    )
    (net (code "11") (name "GPIO1") (class "Default")
      (node (ref "U13") (pin "1") (pinfunction "1_1") (pintype "unspecified"))
      (node (ref "U3") (pin "39") (pinfunction "IO1_39") (pintype "unspecified"))
    )
    (net (code "12") (name "GPIO2") (class "Default")
      (node (ref "U13") (pin "2") (pinfunction "2_2") (pintype "unspecified"))
      (node (ref "U3") (pin "38") (pinfunction "IO2_38") (pintype "unspecified"))
    )
    (net (code "13") (name "GPIO3") (class "Default")
      (node (ref "U14") (pin "1") (pinfunction "1_1") (pintype "unspecified"))
      (node (ref "U3") (pin "15") (pinfunction "IO3_15") (pintype "unspecified"))
    )
    (net (code "14") (name "GPIO4") (class "Default")
      (node (ref "R8") (pin "2") (pinfunction "2_2") (pintype "input"))
      (node (ref "U3") (pin "4") (pinfunction "IO4_4") (pintype "unspecified"))
    )
    (net (code "15") (name "GPIO5") (class "Default")
      (node (ref "R21") (pin "2") (pinfunction "2_2") (pintype "input"))
      (node (ref "U3") (pin "5") (pinfunction "IO5_5") (pintype "unspecified"))
    )
    (net (code "16") (name "GPIO6") (class "Default")
      (node (ref "R9") (pin "2") (pinfunction "2_2") (pintype "input"))
      (node (ref "U3") (pin "6") (pinfunction "IO6_6") (pintype "unspecified"))
    )
    (net (code "17") (name "GPIO7") (class "Default")
      (node (ref "R22") (pin "2") (pinfunction "2_2") (pintype "input"))
      (node (ref "U3") (pin "7") (pinfunction "IO7_7") (pintype "unspecified"))
    )
    (net (code "18") (name "GPIO8") (class "Default")
      (node (ref "U12") (pin "5") (pinfunction "5_5") (pintype "unspecified"))
      (node (ref "U3") (pin "12") (pinfunction "IO8_12") (pintype "unspecified"))
    )
    (net (code "19") (name "GPIO9") (class "Default")
      (node (ref "U14") (pin "3") (pinfunction "3_3") (pintype "unspecified"))
      (node (ref "U3") (pin "17") (pinfunction "IO9_17") (pintype "unspecified"))
    )
    (net (code "20") (name "GPIO10") (class "Default")
      (node (ref "U14") (pin "4") (pinfunction "4_4") (pintype "unspecified"))
      (node (ref "U3") (pin "18") (pinfunction "IO10_18") (pintype "unspecified"))
    )
    (net (code "21") (name "GPIO11") (class "Default")
      (node (ref "U14") (pin "5") (pinfunction "5_5") (pintype "unspecified"))
      (node (ref "U3") (pin "19") (pinfunction "IO11_19") (pintype "unspecified"))
    )
    (net (code "22") (name "GPIO12") (class "Default")
      (node (ref "U14") (pin "6") (pinfunction "6_6") (pintype "unspecified"))
      (node (ref "U3") (pin "20") (pinfunction "IO12_20") (pintype "unspecified"))
    )
    (net (code "23") (name "GPIO13") (class "Default")
      (node (ref "U14") (pin "7") (pinfunction "7_7") (pintype "unspecified"))
      (node (ref "U3") (pin "21") (pinfunction "IO13_21") (pintype "unspecified"))
    )
    (net (code "24") (name "GPIO14") (class "Default")
      (node (ref "U14") (pin "8") (pinfunction "8_8") (pintype "unspecified"))
      (node (ref "U3") (pin "22") (pinfunction "IO14_22") (pintype "unspecified"))
    )
    (net (code "25") (name "GPIO15") (class "Default")
      (node (ref "U12") (pin "1") (pinfunction "1_1") (pintype "unspecified"))
      (node (ref "U3") (pin "8") (pinfunction "IO15_8") (pintype "unspecified"))
    )
    (net (code "26") (name "GPIO16") (class "Default")
      (node (ref "U12") (pin "2") (pinfunction "2_2") (pintype "unspecified"))
      (node (ref "U3") (pin "9") (pinfunction "IO16_9") (pintype "unspecified"))
    )
    (net (code "27") (name "GPIO17") (class "Default")
      (node (ref "U12") (pin "3") (pinfunction "3_3") (pintype "unspecified"))
      (node (ref "U3") (pin "10") (pinfunction "IO17_10") (pintype "unspecified"))
    )
    (net (code "28") (name "GPIO18") (class "Default")
      (node (ref "U12") (pin "4") (pinfunction "4_4") (pintype "unspecified"))
      (node (ref "U3") (pin "11") (pinfunction "IO18_11") (pintype "unspecified"))
    )
    (net (code "29") (name "GPIO19") (class "Default")
      (node (ref "U12") (pin "6") (pinfunction "6_6") (pintype "unspecified"))
      (node (ref "U3") (pin "13") (pinfunction "IO19/USB_D-_13") (pintype "unspecified"))
    )
    (net (code "30") (name "GPIO20") (class "Default")
      (node (ref "U12") (pin "7") (pinfunction "7_7") (pintype "unspecified"))
      (node (ref "U3") (pin "14") (pinfunction "IO20/USB_D+_14") (pintype "unspecified"))
    )
    (net (code "31") (name "GPIO21") (class "Default")
      (node (ref "U14") (pin "9") (pinfunction "9_9") (pintype "unspecified"))
      (node (ref "U3") (pin "23") (pinfunction "IO21_23") (pintype "unspecified"))
    )
    (net (code "32") (name "GPIO35") (class "Default")
      (node (ref "RGB") (pin "4") (pinfunction "DIN_4") (pintype "unspecified"))
      (node (ref "U13") (pin "10") (pinfunction "10_10") (pintype "unspecified"))
      (node (ref "U3") (pin "28") (pinfunction "IO35_28") (pintype "unspecified"))
    )
    (net (code "33") (name "GPIO36") (class "Default")
      (node (ref "U13") (pin "9") (pinfunction "9_9") (pintype "unspecified"))
      (node (ref "U3") (pin "29") (pinfunction "IO36_29") (pintype "unspecified"))
    )
    (net (code "34") (name "GPIO37") (class "Default")
      (node (ref "U13") (pin "8") (pinfunction "8_8") (pintype "unspecified"))
      (node (ref "U3") (pin "30") (pinfunction "IO37_30") (pintype "unspecified"))
    )
    (net (code "35") (name "GPIO38") (class "Default")
      (node (ref "U13") (pin "7") (pinfunction "7_7") (pintype "unspecified"))
      (node (ref "U3") (pin "31") (pinfunction "IO38_31") (pintype "unspecified"))
    )
    (net (code "36") (name "GPIO39") (class "Default")
      (node (ref "U13") (pin "6") (pinfunction "6_6") (pintype "unspecified"))
      (node (ref "U3") (pin "32") (pinfunction "IO39_32") (pintype "unspecified"))
    )
    (net (code "37") (name "GPIO40") (class "Default")
      (node (ref "U13") (pin "5") (pinfunction "5_5") (pintype "unspecified"))
      (node (ref "U3") (pin "33") (pinfunction "IO40_33") (pintype "unspecified"))
    )
    (net (code "38") (name "GPIO41") (class "Default")
      (node (ref "U13") (pin "4") (pinfunction "4_4") (pintype "unspecified"))
      (node (ref "U3") (pin "34") (pinfunction "IO41_34") (pintype "unspecified"))
    )
    (net (code "39") (name "GPIO42") (class "Default")
      (node (ref "U13") (pin "3") (pinfunction "3_3") (pintype "unspecified"))
      (node (ref "U3") (pin "35") (pinfunction "IO42_35") (pintype "unspecified"))
    )
    (net (code "40") (name "GPIO45") (class "Default")
      (node (ref "U14") (pin "12") (pinfunction "12_12") (pintype "unspecified"))
      (node (ref "U3") (pin "26") (pinfunction "IO45_26") (pintype "unspecified"))
    )
    (net (code "41") (name "GPIO46") (class "Default")
      (node (ref "U14") (pin "2") (pinfunction "2_2") (pintype "unspecified"))
      (node (ref "U3") (pin "16") (pinfunction "IO46_16") (pintype "unspecified"))
    )
    (net (code "42") (name "GPIO47") (class "Default")
      (node (ref "U14") (pin "10") (pinfunction "10_10") (pintype "unspecified"))
      (node (ref "U3") (pin "24") (pinfunction "IO47_24") (pintype "unspecified"))
    )
    (net (code "43") (name "GPIO48") (class "Default")
      (node (ref "U14") (pin "11") (pinfunction "11_11") (pintype "unspecified"))
      (node (ref "U3") (pin "25") (pinfunction "IO48_25") (pintype "unspecified"))
    )
    (net (code "44") (name "Net-(D1-A)") (class "Default")
      (node (ref "D1") (pin "2") (pinfunction "A_2") (pintype "unspecified"))
      (node (ref "K1") (pin "1") (pinfunction "1_1") (pintype "unspecified"))
      (node (ref "Q1") (pin "3") (pinfunction "C_3") (pintype "input"))
    )
    (net (code "45") (name "Net-(D2-A)") (class "Default")
      (node (ref "D2") (pin "2") (pinfunction "A_2") (pintype "unspecified"))
      (node (ref "K2") (pin "1") (pinfunction "1_1") (pintype "unspecified"))
      (node (ref "Q2") (pin "3") (pinfunction "C_3") (pintype "input"))
    )
    (net (code "46") (name "Net-(D3-A)") (class "Default")
      (node (ref "D3") (pin "2") (pinfunction "A_2") (pintype "unspecified"))
      (node (ref "K3") (pin "1") (pinfunction "1_1") (pintype "unspecified"))
      (node (ref "Q5") (pin "3") (pinfunction "C_3") (pintype "input"))
    )
    (net (code "47") (name "Net-(D4-A)") (class "Default")
      (node (ref "D4") (pin "2") (pinfunction "A_2") (pintype "unspecified"))
      (node (ref "K4") (pin "1") (pinfunction "1_1") (pintype "unspecified"))
      (node (ref "Q6") (pin "3") (pinfunction "C_3") (pintype "input"))
    )
    (net (code "48") (name "Net-(GREEN-+)") (class "Default")
      (node (ref "GREEN") (pin "1") (pinfunction "+_1") (pintype "unspecified"))
      (node (ref "R4") (pin "1") (pinfunction "1_1") (pintype "input"))
    )
    (net (code "49") (name "Net-(GREEN--)") (class "Default")
      (node (ref "GREEN") (pin "2") (pinfunction "-_2") (pintype "unspecified"))
      (node (ref "Q3") (pin "3") (pinfunction "C_3") (pintype "input"))
      (node (ref "U4") (pin "2") (pinfunction "CAT_2") (pintype "unspecified"))
    )
    (net (code "50") (name "Net-(GREEN1-+)") (class "Default")
      (node (ref "GREEN1") (pin "1") (pinfunction "+_1") (pintype "unspecified"))
      (node (ref "R5") (pin "1") (pinfunction "1_1") (pintype "input"))
    )
    (net (code "51") (name "Net-(GREEN1--)") (class "Default")
      (node (ref "GREEN1") (pin "2") (pinfunction "-_2") (pintype "unspecified"))
      (node (ref "Q4") (pin "3") (pinfunction "C_3") (pintype "input"))
      (node (ref "U5") (pin "2") (pinfunction "CAT_2") (pintype "unspecified"))
    )
    (net (code "52") (name "Net-(GREEN2-+)") (class "Default")
      (node (ref "GREEN2") (pin "1") (pinfunction "+_1") (pintype "unspecified"))
      (node (ref "R16") (pin "1") (pinfunction "1_1") (pintype "input"))
    )
    (net (code "53") (name "Net-(GREEN2--)") (class "Default")
      (node (ref "GREEN2") (pin "2") (pinfunction "-_2") (pintype "unspecified"))
      (node (ref "Q7") (pin "3") (pinfunction "C_3") (pintype "input"))
      (node (ref "U8") (pin "2") (pinfunction "CAT_2") (pintype "unspecified"))
    )
    (net (code "54") (name "Net-(GREEN3-+)") (class "Default")
      (node (ref "GREEN3") (pin "1") (pinfunction "+_1") (pintype "unspecified"))
      (node (ref "R17") (pin "1") (pinfunction "1_1") (pintype "input"))
    )
    (net (code "55") (name "Net-(GREEN3--)") (class "Default")
      (node (ref "GREEN3") (pin "2") (pinfunction "-_2") (pintype "unspecified"))
      (node (ref "Q8") (pin "3") (pinfunction "C_3") (pintype "input"))
      (node (ref "U9") (pin "2") (pinfunction "CAT_2") (pintype "unspecified"))
    )
    (net (code "56") (name "Net-(K1-COM)") (class "Default")
      (node (ref "K1") (pin "2") (pinfunction "COM_2") (pintype "unspecified"))
      (node (ref "U1") (pin "2") (pinfunction "2_2") (pintype "unspecified"))
    )
    (net (code "57") (name "Net-(K1-N.C.)") (class "Default")
      (node (ref "K1") (pin "4") (pinfunction "N.C._4") (pintype "unspecified"))
      (node (ref "U1") (pin "1") (pinfunction "1_1") (pintype "unspecified"))
    )
    (net (code "58") (name "Net-(K1-N.O.)") (class "Default")
      (node (ref "K1") (pin "3") (pinfunction "N.O._3") (pintype "unspecified"))
      (node (ref "U1") (pin "3") (pinfunction "3_3") (pintype "unspecified"))
    )
    (net (code "59") (name "Net-(K2-COM)") (class "Default")
      (node (ref "K2") (pin "2") (pinfunction "COM_2") (pintype "unspecified"))
      (node (ref "U2") (pin "2") (pinfunction "2_2") (pintype "unspecified"))
    )
    (net (code "60") (name "Net-(K2-N.C.)") (class "Default")
      (node (ref "K2") (pin "4") (pinfunction "N.C._4") (pintype "unspecified"))
      (node (ref "U2") (pin "1") (pinfunction "1_1") (pintype "unspecified"))
    )
    (net (code "61") (name "Net-(K2-N.O.)") (class "Default")
      (node (ref "K2") (pin "3") (pinfunction "N.O._3") (pintype "unspecified"))
      (node (ref "U2") (pin "3") (pinfunction "3_3") (pintype "unspecified"))
    )
    (net (code "62") (name "Net-(K3-COM)") (class "Default")
      (node (ref "K3") (pin "2") (pinfunction "COM_2") (pintype "unspecified"))
      (node (ref "U6") (pin "2") (pinfunction "2_2") (pintype "unspecified"))
    )
    (net (code "63") (name "Net-(K3-N.C.)") (class "Default")
      (node (ref "K3") (pin "4") (pinfunction "N.C._4") (pintype "unspecified"))
      (node (ref "U6") (pin "1") (pinfunction "1_1") (pintype "unspecified"))
    )
    (net (code "64") (name "Net-(K3-N.O.)") (class "Default")
      (node (ref "K3") (pin "3") (pinfunction "N.O._3") (pintype "unspecified"))
      (node (ref "U6") (pin "3") (pinfunction "3_3") (pintype "unspecified"))
    )
    (net (code "65") (name "Net-(K4-COM)") (class "Default")
      (node (ref "K4") (pin "2") (pinfunction "COM_2") (pintype "unspecified"))
      (node (ref "U7") (pin "2") (pinfunction "2_2") (pintype "unspecified"))
    )
    (net (code "66") (name "Net-(K4-N.C.)") (class "Default")
      (node (ref "K4") (pin "4") (pinfunction "N.C._4") (pintype "unspecified"))
      (node (ref "U7") (pin "1") (pinfunction "1_1") (pintype "unspecified"))
    )
    (net (code "67") (name "Net-(K4-N.O.)") (class "Default")
      (node (ref "K4") (pin "3") (pinfunction "N.O._3") (pintype "unspecified"))
      (node (ref "U7") (pin "3") (pinfunction "3_3") (pintype "unspecified"))
    )
    (net (code "68") (name "Net-(LED1-A)") (class "Default")
      (node (ref "LED1") (pin "1") (pinfunction "A_1") (pintype "unspecified"))
      (node (ref "R20") (pin "2") (pinfunction "2_2") (pintype "unspecified"))
    )
    (net (code "69") (name "Net-(LED2-+)") (class "Default")
      (node (ref "LED2") (pin "2") (pinfunction "+_2") (pintype "unspecified"))
      (node (ref "R25") (pin "2") (pinfunction "2_2") (pintype "unspecified"))
    )
    (net (code "70") (name "Net-(Q1-B)") (class "Default")
      (node (ref "Q1") (pin "1") (pinfunction "B_1") (pintype "input"))
      (node (ref "R6") (pin "1") (pinfunction "1_1") (pintype "input"))
    )
    (net (code "71") (name "Net-(Q2-B)") (class "Default")
      (node (ref "Q2") (pin "1") (pinfunction "B_1") (pintype "input"))
      (node (ref "R7") (pin "1") (pinfunction "1_1") (pintype "input"))
    )
    (net (code "72") (name "Net-(Q3-B)") (class "Default")
      (node (ref "Q3") (pin "1") (pinfunction "B_1") (pintype "input"))
      (node (ref "R10") (pin "2") (pinfunction "2_2") (pintype "unspecified"))
      (node (ref "R8") (pin "1") (pinfunction "1_1") (pintype "input"))
    )
    (net (code "73") (name "Net-(Q4-B)") (class "Default")
      (node (ref "Q4") (pin "1") (pinfunction "B_1") (pintype "input"))
      (node (ref "R11") (pin "2") (pinfunction "2_2") (pintype "unspecified"))
      (node (ref "R9") (pin "1") (pinfunction "1_1") (pintype "input"))
    )
    (net (code "74") (name "Net-(Q5-B)") (class "Default")
      (node (ref "Q5") (pin "1") (pinfunction "B_1") (pintype "input"))
      (node (ref "R18") (pin "1") (pinfunction "1_1") (pintype "input"))
    )
    (net (code "75") (name "Net-(Q6-B)") (class "Default")
      (node (ref "Q6") (pin "1") (pinfunction "B_1") (pintype "input"))
      (node (ref "R19") (pin "1") (pinfunction "1_1") (pintype "input"))
    )
    (net (code "76") (name "Net-(Q7-B)") (class "Default")
      (node (ref "Q7") (pin "1") (pinfunction "B_1") (pintype "input"))
      (node (ref "R21") (pin "1") (pinfunction "1_1") (pintype "input"))
      (node (ref "R23") (pin "2") (pinfunction "2_2") (pintype "unspecified"))
    )
    (net (code "77") (name "Net-(Q8-B)") (class "Default")
      (node (ref "Q8") (pin "1") (pinfunction "B_1") (pintype "input"))
      (node (ref "R22") (pin "1") (pinfunction "1_1") (pintype "input"))
      (node (ref "R24") (pin "2") (pinfunction "2_2") (pintype "unspecified"))
    )
    (net (code "78") (name "Net-(Q9-B)") (class "Default")
      (node (ref "Q9") (pin "1") (pinfunction "B_1") (pintype "unspecified"))
      (node (ref "R29") (pin "2") (pinfunction "2_2") (pintype "unspecified"))
    )
    (net (code "79") (name "Net-(Q9-C)") (class "Default")
      (node (ref "Q9") (pin "3") (pinfunction "C_3") (pintype "unspecified"))
      (node (ref "R28") (pin "1") (pinfunction "1_1") (pintype "input"))
    )
    (net (code "80") (name "Net-(Q10-D)") (class "Default")
      (node (ref "F1") (pin "2") (pinfunction "2_2") (pintype "unspecified"))
      (node (ref "Q10") (pin "3") (pinfunction "D_3") (pintype "unspecified"))
      (node (ref "U22") (pin "1") (pinfunction "VIN_1") (pintype "unspecified"))
    )
    (net (code "81") (name "Net-(Q10-G)") (class "Default")
      (node (ref "Q10") (pin "1") (pinfunction "G_1") (pintype "unspecified"))
      (node (ref "U22") (pin "5") (pinfunction "GATE_5") (pintype "unspecified"))
    )
    (net (code "82") (name "Net-(Q11-B)") (class "Default")
      (node (ref "Q11") (pin "1") (pinfunction "B_1") (pintype "unspecified"))
      (node (ref "R30") (pin "2") (pinfunction "2_2") (pintype "unspecified"))
    )
    (net (code "83") (name "Net-(Q11-C)") (class "Default")
      (node (ref "Q11") (pin "3") (pinfunction "C_3") (pintype "unspecified"))
      (node (ref "R31") (pin "1") (pinfunction "1_1") (pintype "input"))
    )
    (net (code "84") (name "Net-(RX-+)") (class "Default")
      (node (ref "R27") (pin "2") (pinfunction "2_2") (pintype "unspecified"))
      (node (ref "RX") (pin "1") (pinfunction "+_1") (pintype "unspecified"))
    )
    (net (code "85") (name "Net-(TX-A)") (class "Default")
      (node (ref "R26") (pin "2") (pinfunction "2_2") (pintype "unspecified"))
      (node (ref "TX") (pin "2") (pinfunction "A_2") (pintype "unspecified"))
    )
    (net (code "86") (name "Net-(U4-AN)") (class "Default")
      (node (ref "R2") (pin "1") (pinfunction "1_1") (pintype "input"))
      (node (ref "U4") (pin "1") (pinfunction "AN_1") (pintype "unspecified"))
    )
    (net (code "87") (name "Net-(U4-EMI)") (class "Default")
      (node (ref "R6") (pin "2") (pinfunction "2_2") (pintype "input"))
      (node (ref "U4") (pin "3") (pinfunction "EMI_3") (pintype "unspecified"))
    )
    (net (code "88") (name "Net-(U5-AN)") (class "Default")
      (node (ref "R3") (pin "1") (pinfunction "1_1") (pintype "input"))
      (node (ref "U5") (pin "1") (pinfunction "AN_1") (pintype "unspecified"))
    )
    (net (code "89") (name "Net-(U5-EMI)") (class "Default")
      (node (ref "R7") (pin "2") (pinfunction "2_2") (pintype "input"))
      (node (ref "U5") (pin "3") (pinfunction "EMI_3") (pintype "unspecified"))
    )
    (net (code "90") (name "Net-(U8-AN)") (class "Default")
      (node (ref "R14") (pin "1") (pinfunction "1_1") (pintype "input"))
      (node (ref "U8") (pin "1") (pinfunction "AN_1") (pintype "unspecified"))
    )
    (net (code "91") (name "Net-(U8-EMI)") (class "Default")
      (node (ref "R18") (pin "2") (pinfunction "2_2") (pintype "input"))
      (node (ref "U8") (pin "3") (pinfunction "EMI_3") (pintype "unspecified"))
    )
    (net (code "92") (name "Net-(U9-AN)") (class "Default")
      (node (ref "R15") (pin "1") (pinfunction "1_1") (pintype "input"))
      (node (ref "U9") (pin "1") (pinfunction "AN_1") (pintype "unspecified"))
    )
    (net (code "93") (name "Net-(U9-EMI)") (class "Default")
      (node (ref "R19") (pin "2") (pinfunction "2_2") (pintype "input"))
      (node (ref "U9") (pin "3") (pinfunction "EMI_3") (pintype "unspecified"))
    )
    (net (code "94") (name "Net-(U17-VDD)") (class "Default")
      (node (ref "C4") (pin "2") (pinfunction "2_2") (pintype "unspecified"))
      (node (ref "U17") (pin "6") (pinfunction "VDD_6") (pintype "unspecified"))
    )
    (net (code "95") (name "Net-(U19-Pad1)") (class "Default")
      (node (ref "U19") (pin "1") (pinfunction "1_1") (pintype "unspecified"))
      (node (ref "U20") (pin "2") (pinfunction "AC_2") (pintype "unspecified"))
    )
    (net (code "96") (name "Net-(U19-Pad2)") (class "Default")
      (node (ref "U19") (pin "2") (pinfunction "2_2") (pintype "unspecified"))
      (node (ref "U20") (pin "1") (pinfunction "AC_1") (pintype "unspecified"))
    )
    (net (code "97") (name "Net-(U20--VO)") (class "Default")
      (node (ref "F1") (pin "1") (pinfunction "1_1") (pintype "unspecified"))
      (node (ref "U20") (pin "3") (pinfunction "-VO_3") (pintype "unspecified"))
    )
    (net (code "98") (name "UORXD") (class "Default")
      (node (ref "RX") (pin "2") (pinfunction "-_2") (pintype "unspecified"))
      (node (ref "U17") (pin "26") (pinfunction "TXD_26") (pintype "unspecified"))
      (node (ref "U3") (pin "36") (pinfunction "RXD0_36") (pintype "unspecified"))
    )
    (net (code "99") (name "UOTXD") (class "Default")
      (node (ref "TX") (pin "1") (pinfunction "K_1") (pintype "unspecified"))
      (node (ref "U17") (pin "25") (pinfunction "RXD_25") (pintype "unspecified"))
      (node (ref "U3") (pin "37") (pinfunction "TXD0_37") (pintype "unspecified"))
    )
    (net (code "100") (name "USB_DTR") (class "Default")
      (node (ref "Q11") (pin "2") (pinfunction "E_2") (pintype "unspecified"))
      (node (ref "R29") (pin "1") (pinfunction "1_1") (pintype "unspecified"))
      (node (ref "U17") (pin "28") (pinfunction "DTR_28") (pintype "unspecified"))
    )
    (net (code "101") (name "USB_RTS") (class "Default")
      (node (ref "Q9") (pin "2") (pinfunction "E_2") (pintype "unspecified"))
      (node (ref "R30") (pin "1") (pinfunction "1_1") (pintype "unspecified"))
      (node (ref "U17") (pin "24") (pinfunction "RTS_24") (pintype "unspecified"))
    )
    (net (code "102") (name "VDDUSB") (class "Default")
      (node (ref "C6") (pin "2") (pinfunction "2_2") (pintype "unspecified"))
      (node (ref "C7") (pin "2") (pinfunction "2_2") (pintype "unspecified"))
      (node (ref "C8") (pin "2") (pinfunction "2_2") (pintype "unspecified"))
      (node (ref "D5") (pin "2") (pinfunction "A_2") (pintype "unspecified"))
      (node (ref "D6") (pin "1") (pinfunction "K_1") (pintype "unspecified"))
      (node (ref "U17") (pin "7") (pinfunction "REGIN_7") (pintype "unspecified"))
      (node (ref "U17") (pin "8") (pinfunction "VBUS_8") (pintype "unspecified"))
    )
    (net (code "103") (name "unconnected-(RGB-DOU-Pad2)") (class "Default")
      (node (ref "RGB") (pin "2") (pinfunction "DOU_2") (pintype "unspecified+no_connect"))
    )
    (net (code "104") (name "unconnected-(U17-CTS-Pad23)") (class "Default")
      (node (ref "U17") (pin "23") (pinfunction "CTS_23") (pintype "unspecified+no_connect"))
    )
    (net (code "105") (name "unconnected-(U17-DCD-Pad1)") (class "Default")
      (node (ref "U17") (pin "1") (pinfunction "DCD_1") (pintype "unspecified+no_connect"))
    )
    (net (code "106") (name "unconnected-(U17-DSR-Pad27)") (class "Default")
      (node (ref "U17") (pin "27") (pinfunction "DSR_27") (pintype "unspecified+no_connect"))
    )
    (net (code "107") (name "unconnected-(U17-EP-Pad29)") (class "Default")
      (node (ref "U17") (pin "29") (pinfunction "EP_29") (pintype "unspecified+no_connect"))
    )
    (net (code "108") (name "unconnected-(U17-NC-Pad10)") (class "Default")
      (node (ref "U17") (pin "10") (pinfunction "NC_10") (pintype "unspecified+no_connect"))
    )
    (net (code "109") (name "unconnected-(U17-NC-Pad13)") (class "Default")
      (node (ref "U17") (pin "13") (pinfunction "NC_13") (pintype "unspecified+no_connect"))
    )
    (net (code "110") (name "unconnected-(U17-NC-Pad14)") (class "Default")
      (node (ref "U17") (pin "14") (pinfunction "NC_14") (pintype "unspecified+no_connect"))
    )
    (net (code "111") (name "unconnected-(U17-NC-Pad15)") (class "Default")
      (node (ref "U17") (pin "15") (pinfunction "NC_15") (pintype "unspecified+no_connect"))
    )
    (net (code "112") (name "unconnected-(U17-NC-Pad16)") (class "Default")
      (node (ref "U17") (pin "16") (pinfunction "NC_16") (pintype "unspecified+no_connect"))
    )
    (net (code "113") (name "unconnected-(U17-NC-Pad17)") (class "Default")
      (node (ref "U17") (pin "17") (pinfunction "NC_17") (pintype "unspecified+no_connect"))
    )
    (net (code "114") (name "unconnected-(U17-NC-Pad18)") (class "Default")
      (node (ref "U17") (pin "18") (pinfunction "NC_18") (pintype "unspecified+no_connect"))
    )
    (net (code "115") (name "unconnected-(U17-NC-Pad19)") (class "Default")
      (node (ref "U17") (pin "19") (pinfunction "NC_19") (pintype "unspecified+no_connect"))
    )
    (net (code "116") (name "unconnected-(U17-NC-Pad20)") (class "Default")
      (node (ref "U17") (pin "20") (pinfunction "NC_20") (pintype "unspecified+no_connect"))
    )
    (net (code "117") (name "unconnected-(U17-NC-Pad21)") (class "Default")
      (node (ref "U17") (pin "21") (pinfunction "NC_21") (pintype "unspecified+no_connect"))
    )
    (net (code "118") (name "unconnected-(U17-NC-Pad22)") (class "Default")
      (node (ref "U17") (pin "22") (pinfunction "NC_22") (pintype "unspecified+no_connect"))
    )
    (net (code "119") (name "unconnected-(U17-RI-Pad2)") (class "Default")
      (node (ref "U17") (pin "2") (pinfunction "RI_2") (pintype "unspecified+no_connect"))
    )
    (net (code "120") (name "unconnected-(U17-RST#-Pad9)") (class "Default")
      (node (ref "U17") (pin "9") (pinfunction "RST#_9") (pintype "unspecified+no_connect"))
    )
    (net (code "121") (name "unconnected-(U17-SUSPEND#-Pad11)") (class "Default")
      (node (ref "U17") (pin "11") (pinfunction "SUSPEND#_11") (pintype "unspecified+no_connect"))
    )
    (net (code "122") (name "unconnected-(U17-SUSPEND-Pad12)") (class "Default")
      (node (ref "U17") (pin "12") (pinfunction "SUSPEND_12") (pintype "unspecified+no_connect"))
    )
    (net (code "123") (name "unconnected-(U21-VOUT(TAB)-Pad2)") (class "Default")
      (node (ref "U21") (pin "2") (pinfunction "VOUT(TAB)_2") (pintype "unspecified+no_connect"))
    )
    (net (code "124") (name "unconnected-(U22-STAT-Pad4)") (class "Default")
      (node (ref "U22") (pin "4") (pinfunction "STAT_4") (pintype "unspecified+no_connect"))
    )
    (net (code "125") (name "unconnected-(USB1-SBU1-Pad9)") (class "Default")
      (node (ref "USB1") (pin "9") (pinfunction "SBU1_9") (pintype "unspecified+no_connect"))
    )
    (net (code "126") (name "unconnected-(USB1-SBU2-Pad3)") (class "Default")
      (node (ref "USB1") (pin "3") (pinfunction "SBU2_3") (pintype "unspecified+no_connect"))
    )
    (net (code "127") (name "unconnected-(USB1-SHELL-Pad13)") (class "Default")
      (node (ref "USB1") (pin "13") (pinfunction "SHELL_13") (pintype "unspecified+no_connect"))
    )
    (net (code "128") (name "unconnected-(USB1-SHELL-Pad14)") (class "Default")
      (node (ref "USB1") (pin "14") (pinfunction "SHELL_14") (pintype "unspecified+no_connect"))
    )
  )
)
